# led.net
KiCad netlist of a schematic drawn in Altium Designer
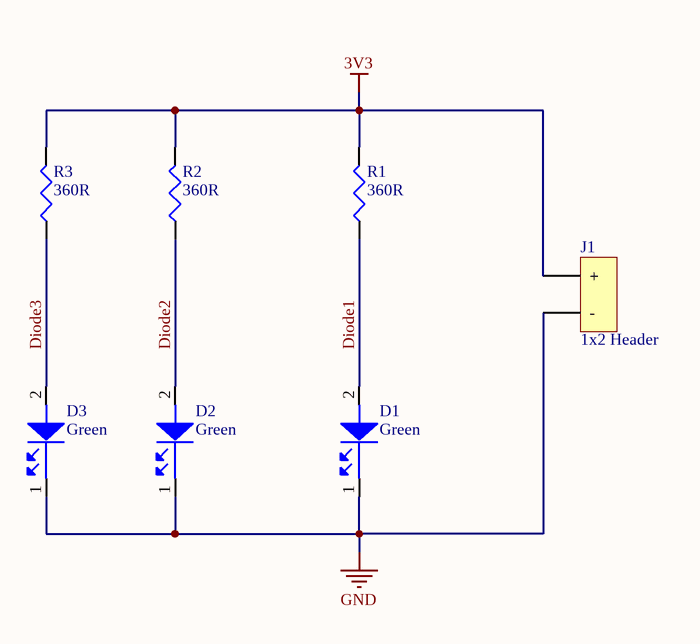
[diagram p0: led.SchDoc]

(export (version "E")
  (design (tool "Eeschema 10.0.6"))
  (components
    (comp (ref "D1")
      (value "Green")
      (footprint "LED0603G")
      (description "Standard LEDs - SMD Green Non-Diffused")
      (fields
        (field (name "MANUFACTURER") "Vishay Semiconductors")
        (field (name "MANUFACTURER PART NUMBER") "TLMG1100-GS08")
      )
      (libsource (lib "led_Schlib") (part "TLMG1100-GS08"))
    )
    (comp (ref "D2")
      (value "Green")
      (footprint "LED0603G")
      (description "Standard LEDs - SMD Green Non-Diffused")
      (fields
        (field (name "MANUFACTURER") "Vishay Semiconductors")
        (field (name "MANUFACTURER PART NUMBER") "TLMG1100-GS08")
      )
      (libsource (lib "led_Schlib") (part "TLMG1100-GS08"))
    )
    (comp (ref "D3")
      (value "Green")
      (footprint "LED0603G")
      (description "Standard LEDs - SMD Green Non-Diffused")
      (fields
        (field (name "MANUFACTURER") "Vishay Semiconductors")
        (field (name "MANUFACTURER PART NUMBER") "TLMG1100-GS08")
      )
      (libsource (lib "led_Schlib") (part "TLMG1100-GS08"))
    )
    (comp (ref "J1")
      (value "1x2 Header")
      (footprint "Header 1X2")
      (description "Conn Wire to Board HDR 2 POS 2.54mm Solder ST Thru-Hole Bag")
      (fields (field (name "MANUFACTURER") "Molex") (field (name "MANUFACTURER PART NUMBER") "22-29-2021"))
      (libsource (lib "led_Schlib") (part "22-29-2021"))
    )
    (comp (ref "R1")
      (value "360R")
      (footprint "Resistor")
      (description "Res Thick Film 0805 360 Ohm 1% 0.125W(1/8W) ±100ppm/C Molded SMD Automotive Paper T/R")
      (fields
        (field (name "MANUFACTURER") "Vishay")
        (field (name "MANUFACTURER PART NUMBER") "CRCW0805360RFKEA")
      )
      (libsource (lib "led_Schlib") (part "CRCW0805360RFKEA"))
    )
    (comp (ref "R2")
      (value "360R")
      (footprint "Resistor")
      (description "Res Thick Film 0805 360 Ohm 1% 0.125W(1/8W) ±100ppm/C Molded SMD Automotive Paper T/R")
      (fields
        (field (name "MANUFACTURER") "Vishay")
        (field (name "MANUFACTURER PART NUMBER") "CRCW0805360RFKEA")
      )
      (libsource (lib "led_Schlib") (part "CRCW0805360RFKEA"))
    )
    (comp (ref "R3")
      (value "360R")
      (footprint "Resistor")
      (description "Res Thick Film 0805 360 Ohm 1% 0.125W(1/8W) ±100ppm/C Molded SMD Automotive Paper T/R")
      (fields
        (field (name "MANUFACTURER") "Vishay")
        (field (name "MANUFACTURER PART NUMBER") "CRCW0805360RFKEA")
      )
      (libsource (lib "led_Schlib") (part "CRCW0805360RFKEA"))
    )
  )
  (nets
    (net (code "1") (name "/Diode1") (class "Default")
      (node (ref "D1") (pin "2") (pinfunction "2_2") (pintype "passive"))
      (node (ref "R1") (pin "1") (pinfunction "1_1") (pintype "passive"))
    )
    (net (code "2") (name "/Diode2") (class "Default")
      (node (ref "D2") (pin "2") (pinfunction "2_2") (pintype "passive"))
      (node (ref "R2") (pin "1") (pinfunction "1_1") (pintype "passive"))
    )
    (net (code "3") (name "/Diode3") (class "Default")
      (node (ref "D3") (pin "2") (pinfunction "2_2") (pintype "passive"))
      (node (ref "R3") (pin "1") (pinfunction "1_1") (pintype "passive"))
    )
    (net (code "4") (name "3V3") (class "Default")
      (node (ref "J1") (pin "1") (pinfunction "+_1") (pintype "passive"))
      (node (ref "R1") (pin "2") (pinfunction "2_2") (pintype "passive"))
      (node (ref "R2") (pin "2") (pinfunction "2_2") (pintype "passive"))
      (node (ref "R3") (pin "2") (pinfunction "2_2") (pintype "passive"))
    )
    (net (code "5") (name "GND") (class "Default")
      (node (ref "D1") (pin "1") (pinfunction "1_1") (pintype "passive"))
      (node (ref "D2") (pin "1") (pinfunction "1_1") (pintype "passive"))
      (node (ref "D3") (pin "1") (pinfunction "1_1") (pintype "passive"))
      (node (ref "J1") (pin "2") (pinfunction "-_2") (pintype "passive"))
    )
  )
)
